# working.net
KiCad netlist of a schematic drawn in EAGLE
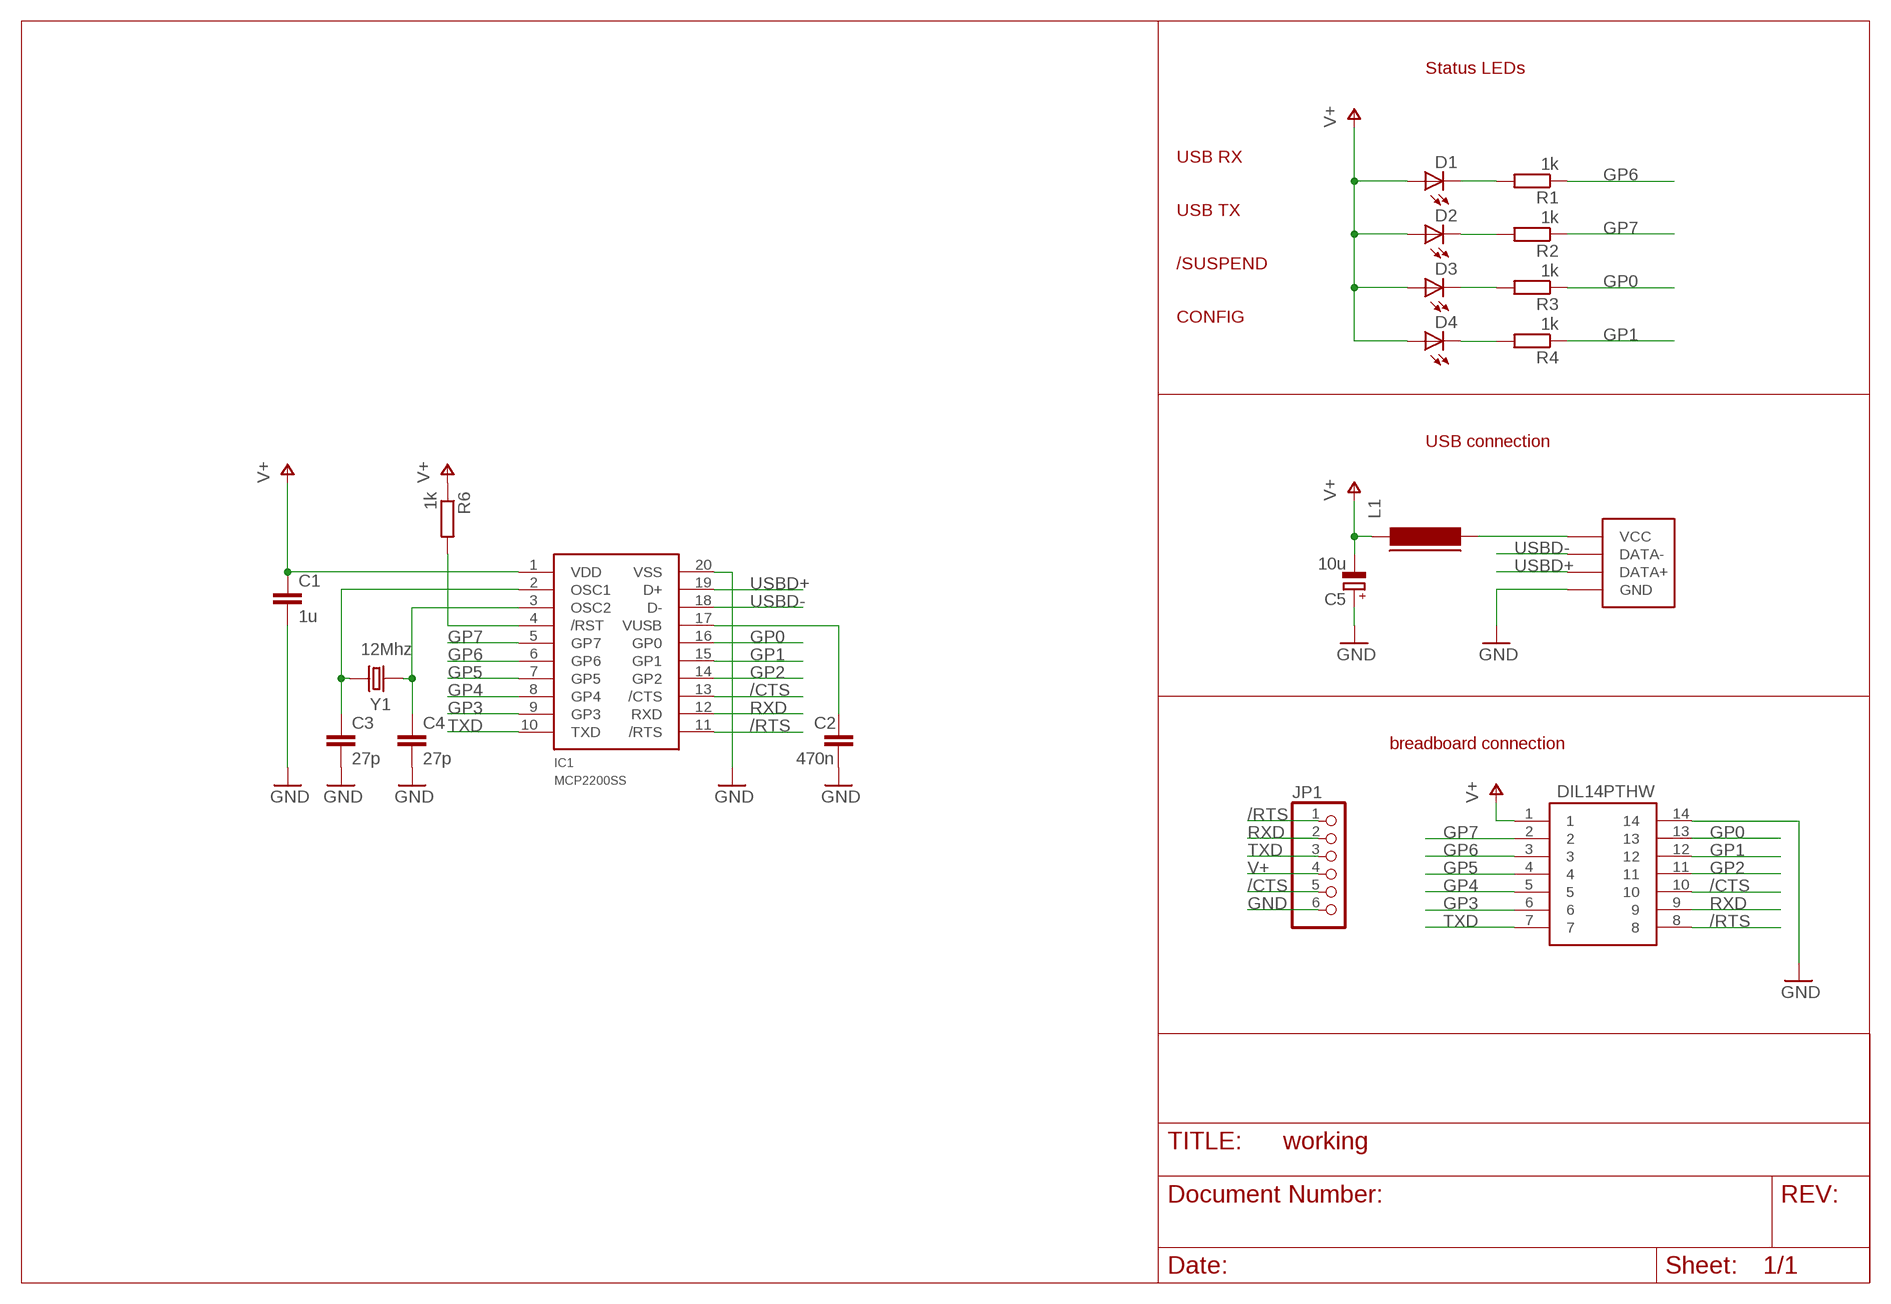
[diagram p0: schematic, sheet 1]

(export (version "E")
  (design (tool "Eeschema 10.0.6"))
  (components
    (comp (ref "C1")
      (value "1u")
      (footprint "eagle-import:C805")
      (libsource (lib "eagle-import") (part "CAPC805"))
    )
    (comp (ref "C2")
      (value "470n")
      (footprint "eagle-import:C805")
      (libsource (lib "eagle-import") (part "CAPC805"))
    )
    (comp (ref "C3")
      (value "27p")
      (footprint "eagle-import:C805")
      (libsource (lib "eagle-import") (part "CAPC805"))
    )
    (comp (ref "C4")
      (value "27p")
      (footprint "eagle-import:C805")
      (libsource (lib "eagle-import") (part "CAPC805"))
    )
    (comp (ref "C5")
      (value "10u")
      (footprint "eagle-import:SMC_A")
      (libsource (lib "eagle-import") (part "CAP_POLSMC_A"))
    )
    (comp (ref "D1")
      (value "LED805")
      (footprint "eagle-import:LED-805")
      (libsource (lib "eagle-import") (part "LED805"))
    )
    (comp (ref "D2")
      (value "LED805")
      (footprint "eagle-import:LED-805")
      (libsource (lib "eagle-import") (part "LED805"))
    )
    (comp (ref "D3")
      (value "LED805")
      (footprint "eagle-import:LED-805")
      (libsource (lib "eagle-import") (part "LED805"))
    )
    (comp (ref "D4")
      (value "LED805")
      (footprint "eagle-import:LED-805")
      (libsource (lib "eagle-import") (part "LED805"))
    )
    (comp (ref "IC1")
      (value "MCP2200SS")
      (footprint "eagle-import:SSOP20")
      (libsource (lib "eagle-import") (part "MCP2200SS"))
    )
    (comp (ref "JP1")
      (value "PINHD-1X6")
      (footprint "eagle-import:1X06")
      (libsource (lib "eagle-import") (part "PINHD-1X6"))
    )
    (comp (ref "L1")
      (value "FERRITE_BEAD805")
      (footprint "eagle-import:FB805")
      (libsource (lib "eagle-import") (part "FERRITE_BEAD805"))
    )
    (comp (ref "R1")
      (value "1k")
      (footprint "eagle-import:R805")
      (libsource (lib "eagle-import") (part "RESISTORR805R805"))
    )
    (comp (ref "R2")
      (value "1k")
      (footprint "eagle-import:R805")
      (libsource (lib "eagle-import") (part "RESISTORR805R805"))
    )
    (comp (ref "R3")
      (value "1k")
      (footprint "eagle-import:R805")
      (libsource (lib "eagle-import") (part "RESISTORR805R805"))
    )
    (comp (ref "R4")
      (value "1k")
      (footprint "eagle-import:R805")
      (libsource (lib "eagle-import") (part "RESISTORR805R805"))
    )
    (comp (ref "R6")
      (value "1k")
      (footprint "eagle-import:R805")
      (libsource (lib "eagle-import") (part "RESISTORR805R805"))
    )
    (comp (ref "U$1")
      (value "DIL14PTHW")
      (footprint "eagle-import:DIP14W")
      (libsource (lib "eagle-import") (part "DIL14PTHW"))
    )
    (comp (ref "X1")
      (value "MINI-USBUSB2")
      (footprint "eagle-import:CONN_MINI_USB_B")
      (libsource (lib "eagle-import") (part "MINI-USBUSB2"))
    )
    (comp (ref "Y1")
      (value "12Mhz")
      (footprint "eagle-import:4X6")
      (libsource (lib "eagle-import") (part "CRYSTAL_212M_"))
    )
  )
  (nets
    (net (code "1") (name "/GP0") (class "Default")
      (node (ref "IC1") (pin "16") (pinfunction "GP0_16") (pintype "bidirectional"))
      (node (ref "R3") (pin "1") (pinfunction "1_1") (pintype "passive"))
      (node (ref "U$1") (pin "13") (pinfunction "13_13") (pintype "bidirectional"))
    )
    (net (code "2") (name "/GP1") (class "Default")
      (node (ref "IC1") (pin "15") (pinfunction "GP1_15") (pintype "bidirectional"))
      (node (ref "R4") (pin "1") (pinfunction "1_1") (pintype "passive"))
      (node (ref "U$1") (pin "12") (pinfunction "12_12") (pintype "bidirectional"))
    )
    (net (code "3") (name "/GP2") (class "Default")
      (node (ref "IC1") (pin "14") (pinfunction "GP2_14") (pintype "bidirectional"))
      (node (ref "U$1") (pin "11") (pinfunction "11_11") (pintype "bidirectional"))
    )
    (net (code "4") (name "/GP3") (class "Default")
      (node (ref "IC1") (pin "9") (pinfunction "GP3_9") (pintype "bidirectional"))
      (node (ref "U$1") (pin "6") (pinfunction "6_6") (pintype "bidirectional"))
    )
    (net (code "5") (name "/GP4") (class "Default")
      (node (ref "IC1") (pin "8") (pinfunction "GP4_8") (pintype "bidirectional"))
      (node (ref "U$1") (pin "5") (pinfunction "5_5") (pintype "bidirectional"))
    )
    (net (code "6") (name "/GP5") (class "Default")
      (node (ref "IC1") (pin "7") (pinfunction "GP5_7") (pintype "bidirectional"))
      (node (ref "U$1") (pin "4") (pinfunction "4_4") (pintype "bidirectional"))
    )
    (net (code "7") (name "/GP6") (class "Default")
      (node (ref "IC1") (pin "6") (pinfunction "GP6_6") (pintype "bidirectional"))
      (node (ref "R1") (pin "1") (pinfunction "1_1") (pintype "passive"))
      (node (ref "U$1") (pin "3") (pinfunction "3_3") (pintype "bidirectional"))
    )
    (net (code "8") (name "/GP7") (class "Default")
      (node (ref "IC1") (pin "5") (pinfunction "GP7_5") (pintype "bidirectional"))
      (node (ref "R2") (pin "1") (pinfunction "1_1") (pintype "passive"))
      (node (ref "U$1") (pin "2") (pinfunction "2_2") (pintype "bidirectional"))
    )
    (net (code "9") (name "/RXD") (class "Default")
      (node (ref "IC1") (pin "12") (pinfunction "RXD_12") (pintype "bidirectional"))
      (node (ref "JP1") (pin "2") (pinfunction "2_2") (pintype "passive"))
      (node (ref "U$1") (pin "9") (pinfunction "9_9") (pintype "bidirectional"))
    )
    (net (code "10") (name "/TXD") (class "Default")
      (node (ref "IC1") (pin "10") (pinfunction "TXD_10") (pintype "bidirectional"))
      (node (ref "JP1") (pin "3") (pinfunction "3_3") (pintype "passive"))
      (node (ref "U$1") (pin "7") (pinfunction "7_7") (pintype "bidirectional"))
    )
    (net (code "11") (name "/USBD+") (class "Default")
      (node (ref "IC1") (pin "19") (pinfunction "D+_19") (pintype "bidirectional"))
      (node (ref "X1") (pin "D+") (pinfunction "DATA+_D+") (pintype "bidirectional"))
    )
    (net (code "12") (name "/USBD-") (class "Default")
      (node (ref "IC1") (pin "18") (pinfunction "D-_18") (pintype "bidirectional"))
      (node (ref "X1") (pin "D-") (pinfunction "DATA-_D-") (pintype "bidirectional"))
    )
    (net (code "13") (name "/{slash}CTS") (class "Default")
      (node (ref "IC1") (pin "13") (pinfunction "/CTS_13") (pintype "bidirectional"))
      (node (ref "JP1") (pin "5") (pinfunction "5_5") (pintype "passive"))
      (node (ref "U$1") (pin "10") (pinfunction "10_10") (pintype "bidirectional"))
    )
    (net (code "14") (name "/{slash}RTS") (class "Default")
      (node (ref "IC1") (pin "11") (pinfunction "/RTS_11") (pintype "bidirectional"))
      (node (ref "JP1") (pin "1") (pinfunction "1_1") (pintype "passive"))
      (node (ref "U$1") (pin "8") (pinfunction "8_8") (pintype "bidirectional"))
    )
    (net (code "15") (name "GND") (class "Default")
      (node (ref "C1") (pin "2") (pinfunction "2_2") (pintype "passive"))
      (node (ref "C2") (pin "2") (pinfunction "2_2") (pintype "passive"))
      (node (ref "C3") (pin "2") (pinfunction "2_2") (pintype "passive"))
      (node (ref "C4") (pin "2") (pinfunction "2_2") (pintype "passive"))
      (node (ref "C5") (pin "+") (pinfunction "+_+") (pintype "passive"))
      (node (ref "IC1") (pin "20") (pinfunction "VSS_20") (pintype "bidirectional"))
      (node (ref "JP1") (pin "6") (pinfunction "6_6") (pintype "passive"))
      (node (ref "U$1") (pin "14") (pinfunction "14_14") (pintype "bidirectional"))
      (node (ref "X1") (pin "GND") (pinfunction "GND_GND") (pintype "bidirectional"))
    )
    (net (code "16") (name "Net-(D1-PadC)") (class "Default")
      (node (ref "D1") (pin "C") (pinfunction "C_C") (pintype "passive"))
      (node (ref "R1") (pin "2") (pinfunction "2_2") (pintype "passive"))
    )
    (net (code "17") (name "Net-(D2-PadC)") (class "Default")
      (node (ref "D2") (pin "C") (pinfunction "C_C") (pintype "passive"))
      (node (ref "R2") (pin "2") (pinfunction "2_2") (pintype "passive"))
    )
    (net (code "18") (name "Net-(D3-PadC)") (class "Default")
      (node (ref "D3") (pin "C") (pinfunction "C_C") (pintype "passive"))
      (node (ref "R3") (pin "2") (pinfunction "2_2") (pintype "passive"))
    )
    (net (code "19") (name "Net-(D4-PadC)") (class "Default")
      (node (ref "D4") (pin "C") (pinfunction "C_C") (pintype "passive"))
      (node (ref "R4") (pin "2") (pinfunction "2_2") (pintype "passive"))
    )
    (net (code "20") (name "Net-(IC1-OSC1)") (class "Default")
      (node (ref "C3") (pin "1") (pinfunction "1_1") (pintype "passive"))
      (node (ref "IC1") (pin "2") (pinfunction "OSC1_2") (pintype "bidirectional"))
      (node (ref "Y1") (pin "2") (pinfunction "X2_2") (pintype "bidirectional"))
    )
    (net (code "21") (name "Net-(IC1-OSC2)") (class "Default")
      (node (ref "C4") (pin "1") (pinfunction "1_1") (pintype "passive"))
      (node (ref "IC1") (pin "3") (pinfunction "OSC2_3") (pintype "bidirectional"))
      (node (ref "Y1") (pin "1") (pinfunction "X1_1") (pintype "bidirectional"))
    )
    (net (code "22") (name "Net-(IC1-VUSB)") (class "Default")
      (node (ref "C2") (pin "1") (pinfunction "1_1") (pintype "passive"))
      (node (ref "IC1") (pin "17") (pinfunction "VUSB_17") (pintype "bidirectional"))
    )
    (net (code "23") (name "Net-(IC1-{slash}RST)") (class "Default")
      (node (ref "IC1") (pin "4") (pinfunction "/RST_4") (pintype "bidirectional"))
      (node (ref "R6") (pin "2") (pinfunction "2_2") (pintype "passive"))
    )
    (net (code "24") (name "Net-(X1-VCC)") (class "Default")
      (node (ref "L1") (pin "2") (pinfunction "2_2") (pintype "passive"))
      (node (ref "X1") (pin "VUSB") (pinfunction "VCC_VUSB") (pintype "bidirectional"))
    )
    (net (code "25") (name "V+") (class "Default")
      (node (ref "C1") (pin "1") (pinfunction "1_1") (pintype "passive"))
      (node (ref "C5") (pin "-") (pinfunction "-_-") (pintype "passive"))
      (node (ref "D1") (pin "A") (pinfunction "A_A") (pintype "passive"))
      (node (ref "D2") (pin "A") (pinfunction "A_A") (pintype "passive"))
      (node (ref "D3") (pin "A") (pinfunction "A_A") (pintype "passive"))
      (node (ref "D4") (pin "A") (pinfunction "A_A") (pintype "passive"))
      (node (ref "IC1") (pin "1") (pinfunction "VDD_1") (pintype "bidirectional"))
      (node (ref "JP1") (pin "4") (pinfunction "4_4") (pintype "passive"))
      (node (ref "L1") (pin "1") (pinfunction "1_1") (pintype "passive"))
      (node (ref "R6") (pin "1") (pinfunction "1_1") (pintype "passive"))
      (node (ref "U$1") (pin "1") (pinfunction "1_1") (pintype "bidirectional"))
    )
  )
)
